# USB-interface.net
KiCad netlist of a schematic drawn in Altium Designer
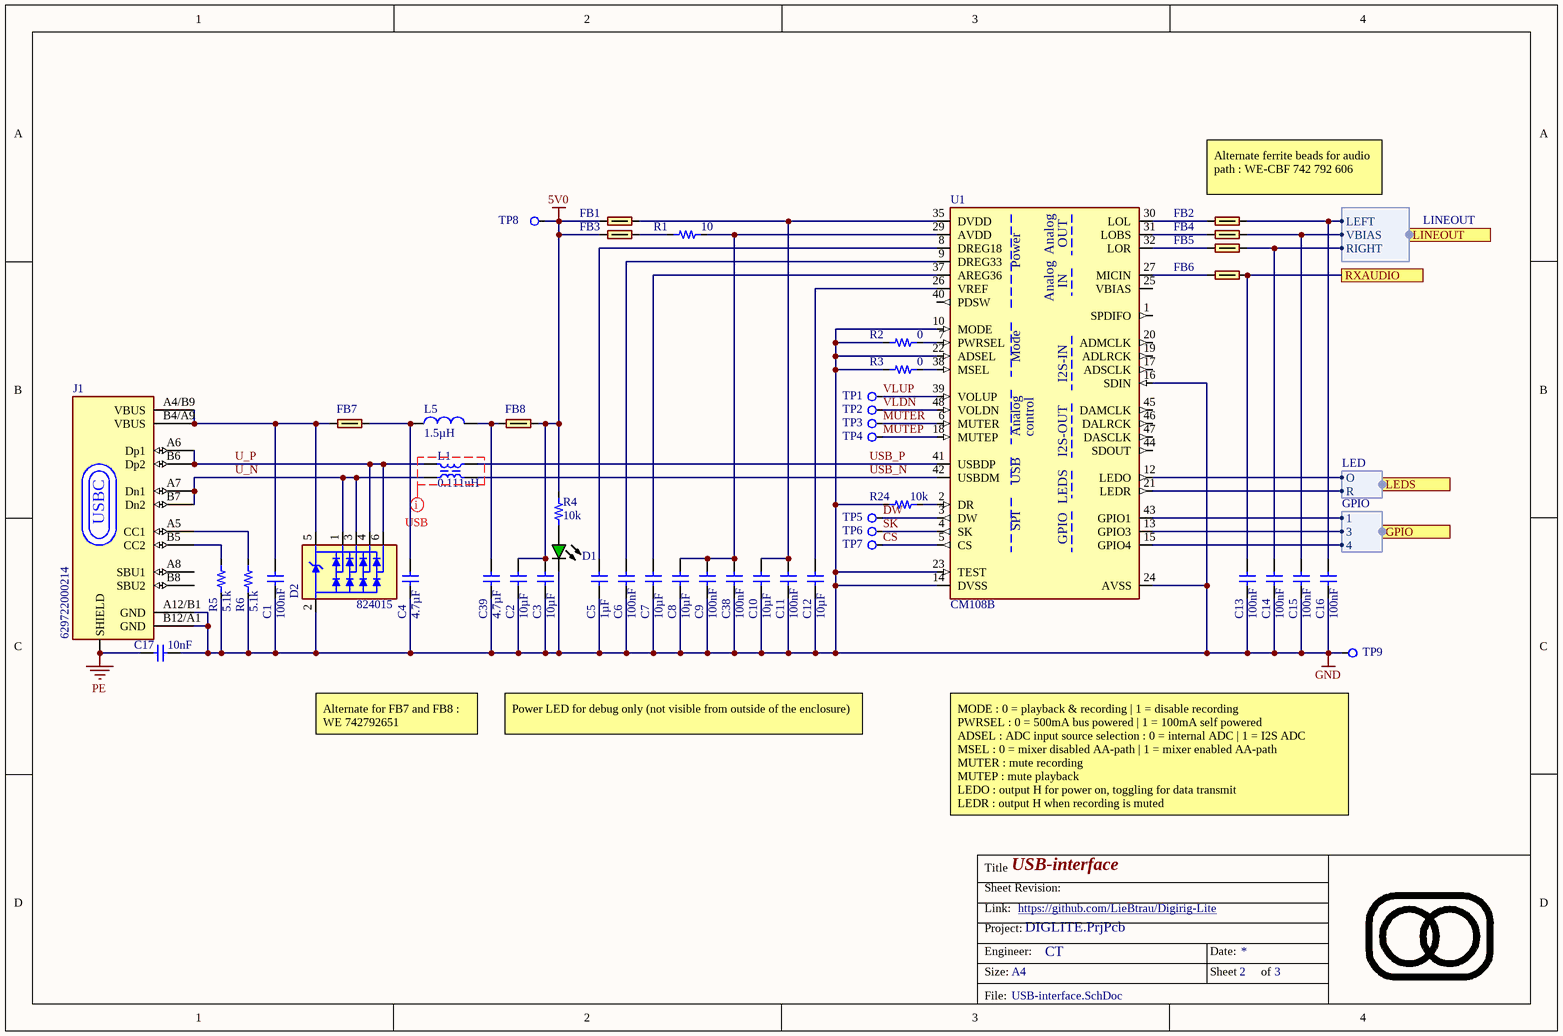
[diagram p0: USB-interface.SchDoc]

(export (version "E")
  (design (tool "Eeschema 10.0.6"))
  (components
    (comp (ref "C1")
      (value "100nF")
      (footprint "0603-C-N")
      (description "WCAP-CSGP Multilayer Ceramic Chip Capacitor, General Purpose, size 0603, X7R, 100nF, 50VDC")
      (fields (field (name "TOLERANCE") "10%") (field (name "JLCPCB PART #") "C14663"))
      (libsource (lib "7c7 Engineering") (part "CAP-NP-2"))
    )
    (comp (ref "C2")
      (value "10µF")
      (footprint "WCAP-CSGP_1210_L3.2W2.5H2.5")
      (description "WCAP-CSGP Multilayer Ceramic Chip Capacitor, General Purpose, size 1210, X7R, 10µF, 50VDC")
      (fields (field (name "TOLERANCE") "10%") (field (name "JLCPCB PART #") "C77102"))
      (libsource (lib "7c7 Engineering") (part "CAP-NP-2"))
    )
    (comp (ref "C3")
      (value "10µF")
      (footprint "WCAP-CSGP_1210_L3.2W2.5H2.5")
      (description "WCAP-CSGP Multilayer Ceramic Chip Capacitor, General Purpose, size 1210, X7R, 10µF, 50VDC")
      (fields (field (name "TOLERANCE") "10%") (field (name "JLCPCB PART #") "C77102"))
      (libsource (lib "7c7 Engineering") (part "CAP-NP-2"))
    )
    (comp (ref "C4")
      (value "4.7µF")
      (footprint "1206-C-N")
      (description "WCAP-CSGP Multilayer Ceramic Chip Capacitor, General Purpose, size 1206, X7R, 4.7µF, 10VDC")
      (fields (field (name "TOLERANCE") "10%") (field (name "JLCPCB BASIC PART") "Yes"))
      (libsource (lib "7c7 Engineering") (part "CAP-NP-2"))
    )
    (comp (ref "C5")
      (value "1µF")
      (footprint "0603-C-N")
      (description "Capacitor MLCC, General Purpose, size 0603, X7R, 1µF, +/-10%, 16V")
      (fields (field (name "TOLERANCE") "10%") (field (name "JLCPCB PART #") "C15849"))
      (libsource (lib "7c7 Engineering") (part "CAP-NP-2"))
    )
    (comp (ref "C6")
      (value "100nF")
      (footprint "0603-C-N")
      (description "WCAP-CSGP Multilayer Ceramic Chip Capacitor, General Purpose, size 0603, X7R, 100nF, 50VDC")
      (fields (field (name "TOLERANCE") "10%") (field (name "JLCPCB PART #") "C14663"))
      (libsource (lib "7c7 Engineering") (part "CAP-NP-2"))
    )
    (comp (ref "C7")
      (value "10µF")
      (footprint "WCAP-CSGP_1210_L3.2W2.5H2.5")
      (description "WCAP-CSGP Multilayer Ceramic Chip Capacitor, General Purpose, size 1210, X7R, 10µF, 50VDC")
      (fields (field (name "TOLERANCE") "10%") (field (name "JLCPCB PART #") "C77102"))
      (libsource (lib "7c7 Engineering") (part "CAP-NP-2"))
    )
    (comp (ref "C8")
      (value "10µF")
      (footprint "WCAP-CSGP_1210_L3.2W2.5H2.5")
      (description "WCAP-CSGP Multilayer Ceramic Chip Capacitor, General Purpose, size 1210, X7R, 10µF, 50VDC")
      (fields (field (name "TOLERANCE") "10%") (field (name "JLCPCB PART #") "C77102"))
      (libsource (lib "7c7 Engineering") (part "CAP-NP-2"))
    )
    (comp (ref "C9")
      (value "100nF")
      (footprint "0603-C-N")
      (description "WCAP-CSGP Multilayer Ceramic Chip Capacitor, General Purpose, size 0603, X7R, 100nF, 50VDC")
      (fields (field (name "TOLERANCE") "10%") (field (name "JLCPCB PART #") "C14663"))
      (libsource (lib "7c7 Engineering") (part "CAP-NP-2"))
    )
    (comp (ref "C10")
      (value "10µF")
      (footprint "WCAP-CSGP_1210_L3.2W2.5H2.5")
      (description "WCAP-CSGP Multilayer Ceramic Chip Capacitor, General Purpose, size 1210, X7R, 10µF, 50VDC")
      (fields (field (name "TOLERANCE") "10%") (field (name "JLCPCB PART #") "C77102"))
      (libsource (lib "7c7 Engineering") (part "CAP-NP-2"))
    )
    (comp (ref "C11")
      (value "100nF")
      (footprint "0603-C-N")
      (description "WCAP-CSGP Multilayer Ceramic Chip Capacitor, General Purpose, size 0603, X7R, 100nF, 50VDC")
      (fields (field (name "TOLERANCE") "10%") (field (name "JLCPCB PART #") "C14663"))
      (libsource (lib "7c7 Engineering") (part "CAP-NP-2"))
    )
    (comp (ref "C12")
      (value "10µF")
      (footprint "WCAP-CSGP_1210_L3.2W2.5H2.5")
      (description "WCAP-CSGP Multilayer Ceramic Chip Capacitor, General Purpose, size 1210, X7R, 10µF, 50VDC")
      (fields (field (name "TOLERANCE") "10%") (field (name "JLCPCB PART #") "C77102"))
      (libsource (lib "7c7 Engineering") (part "CAP-NP-2"))
    )
    (comp (ref "C13")
      (value "100nF")
      (footprint "0603-C-N")
      (description "WCAP-CSGP Multilayer Ceramic Chip Capacitor, General Purpose, size 0603, X7R, 100nF, 50VDC")
      (fields (field (name "TOLERANCE") "10%") (field (name "JLCPCB PART #") "C14663"))
      (libsource (lib "7c7 Engineering") (part "CAP-NP-2"))
    )
    (comp (ref "C14")
      (value "100nF")
      (footprint "0603-C-N")
      (description "WCAP-CSGP Multilayer Ceramic Chip Capacitor, General Purpose, size 0603, X7R, 100nF, 50VDC")
      (fields (field (name "TOLERANCE") "10%") (field (name "JLCPCB PART #") "C14663"))
      (libsource (lib "7c7 Engineering") (part "CAP-NP-2"))
    )
    (comp (ref "C15")
      (value "100nF")
      (footprint "0603-C-N")
      (description "WCAP-CSGP Multilayer Ceramic Chip Capacitor, General Purpose, size 0603, X7R, 100nF, 50VDC")
      (fields (field (name "TOLERANCE") "10%") (field (name "JLCPCB PART #") "C14663"))
      (libsource (lib "7c7 Engineering") (part "CAP-NP-2"))
    )
    (comp (ref "C16")
      (value "100nF")
      (footprint "0603-C-N")
      (description "WCAP-CSGP Multilayer Ceramic Chip Capacitor, General Purpose, size 0603, X7R, 100nF, 50VDC")
      (fields (field (name "TOLERANCE") "10%") (field (name "JLCPCB PART #") "C14663"))
      (libsource (lib "7c7 Engineering") (part "CAP-NP-2"))
    )
    (comp (ref "C17")
      (value "10nF")
      (footprint "0603-C-N")
      (description "Multilayer Ceramic Capacitor, Grm Series, 0.01 F, 5%, C0g / Np0, 50 V, 0603 [1608 Metric]")
      (fields (field (name "VOLTAGE") "50V") (field (name "TOLERANCE") "5%"))
      (libsource (lib "7c7 Engineering") (part "CAP-NP-2"))
    )
    (comp (ref "C38")
      (value "100nF")
      (footprint "0603-C-N")
      (description "WCAP-CSGP Multilayer Ceramic Chip Capacitor, General Purpose, size 0603, X7R, 100nF, 50VDC")
      (fields (field (name "TOLERANCE") "10%") (field (name "JLCPCB PART #") "C14663"))
      (libsource (lib "7c7 Engineering") (part "CAP-NP-2"))
    )
    (comp (ref "C39")
      (value "4.7µF")
      (footprint "1206-C-N")
      (description "WCAP-CSGP Multilayer Ceramic Chip Capacitor, General Purpose, size 1206, X7R, 4.7µF, 10VDC")
      (fields (field (name "TOLERANCE") "10%") (field (name "JLCPCB BASIC PART") "Yes"))
      (libsource (lib "7c7 Engineering") (part "CAP-NP-2"))
    )
    (comp (ref "D1")
      (value "150060GS84000")
      (footprint "WL-SMCW_0603_150060xx8x000")
      (description "WL-SMCW Mono-color Chip LED Waterclear, size 0603, Green, 3.3V, 40°")
      (fields (field (name "JLCPCB PART #") "C7429914") (field (name "MANUFACTURER") "Wurth Elektronik"))
      (libsource (lib "7c7 Engineering") (part "LED-GREEN-2"))
    )
    (comp (ref "D2")
      (value "824015")
      (footprint "SOT-23-6")
      (description "WE-TVS TVS Diode - High Speed Series, SOT23-6L, 4+1Channel, 5Vdc")
      (fields (field (name "FLIR PART #") "YDITA20KV100A") (field (name "JLCPCB PART #") "C558418"))
      (libsource (lib "7c7 Engineering") (part "D-TVS-4CH"))
    )
    (comp (ref "FB1")
      (value "742792662")
      (footprint "0603-FB-N")
      (description "WE-CBF SMT EMI Suppression Ferrite Bead, size 0603, 1000O, 0.83A")
      (fields (field (name "JLCPCB PART #") "C180490") (field (name "MANUFACTURER") "Wurth Elektronik"))
      (libsource (lib "7c7 Engineering") (part "IND_BEAD"))
    )
    (comp (ref "FB2")
      (value "742792662")
      (footprint "0603-FB-N")
      (description "WE-CBF SMT EMI Suppression Ferrite Bead, size 0603, 1000O, 0.83A")
      (fields (field (name "JLCPCB PART #") "C180490") (field (name "MANUFACTURER") "Wurth Elektronik"))
      (libsource (lib "7c7 Engineering") (part "IND_BEAD"))
    )
    (comp (ref "FB3")
      (value "742792662")
      (footprint "0603-FB-N")
      (description "WE-CBF SMT EMI Suppression Ferrite Bead, size 0603, 1000O, 0.83A")
      (fields (field (name "JLCPCB PART #") "C180490") (field (name "MANUFACTURER") "Wurth Elektronik"))
      (libsource (lib "7c7 Engineering") (part "IND_BEAD"))
    )
    (comp (ref "FB4")
      (value "742792662")
      (footprint "0603-FB-N")
      (description "WE-CBF SMT EMI Suppression Ferrite Bead, size 0603, 1000O, 0.83A")
      (fields (field (name "JLCPCB PART #") "C180490") (field (name "MANUFACTURER") "Wurth Elektronik"))
      (libsource (lib "7c7 Engineering") (part "IND_BEAD"))
    )
    (comp (ref "FB5")
      (value "742792662")
      (footprint "0603-FB-N")
      (description "WE-CBF SMT EMI Suppression Ferrite Bead, size 0603, 1000O, 0.83A")
      (fields (field (name "JLCPCB PART #") "C180490") (field (name "MANUFACTURER") "Wurth Elektronik"))
      (libsource (lib "7c7 Engineering") (part "IND_BEAD"))
    )
    (comp (ref "FB6")
      (value "742792662")
      (footprint "0603-FB-N")
      (description "WE-CBF SMT EMI Suppression Ferrite Bead, size 0603, 1000O, 0.83A")
      (fields (field (name "JLCPCB PART #") "C180490") (field (name "MANUFACTURER") "Wurth Elektronik"))
      (libsource (lib "7c7 Engineering") (part "IND_BEAD"))
    )
    (comp (ref "FB7")
      (value "74279221111")
      (footprint "WE-CBF_1206_Medium Current")
      (description "Ferrite Beads Multi-Layer High Current 110Ohm 25% 100MHz 5.4A 0.015Ohm DCR 1206 T/R")
      (fields (field (name "JLCPCB PART #") "C85841") (field (name "MANUFACTURER") "Wurth Elektronik"))
      (libsource (lib "7c7 Engineering") (part "IND_BEAD"))
    )
    (comp (ref "FB8")
      (value "74279221111")
      (footprint "WE-CBF_1206_Medium Current")
      (description "Ferrite Beads Multi-Layer High Current 110Ohm 25% 100MHz 5.4A 0.015Ohm DCR 1206 T/R")
      (fields (field (name "JLCPCB PART #") "C85841") (field (name "MANUFACTURER") "Wurth Elektronik"))
      (libsource (lib "7c7 Engineering") (part "IND_BEAD"))
    )
    (comp (ref "J1")
      (value "629722000214")
      (footprint "629722000214")
      (description "WR-USB 2.0 Type C, Receptacle, Horizontal, SMT")
      (fields (field (name "MANUFACTURER") "Wurth Elektronik") (field (name "JLCPCB PART #") "C2982555"))
      (libsource (lib "7c7 Engineering") (part "629722000214"))
    )
    (comp (ref "L1")
      (value "744232090")
      (footprint "WE-CNSW_1206")
      (description "WE-CNSW SMT Common Mode Line Filter, size 1206, 90Ohm, 0.111uH, 50V")
      (fields (field (name "JLCPCB PART #") "C131487") (field (name "INDUCTANCE") "0.111uH"))
      (libsource (lib "7c7 Engineering") (part "CM-choke"))
    )
    (comp (ref "L5")
      (value "1.5µH")
      (footprint "WE-MAPI_2512")
      (description "Inductor Power Shielded Wirewound 1.5uH 20% 100KHz Powdered Iron 2.2A 99mOhm DCR 1008 T/R")
      (fields (field (name "TOLERANCE") "20%") (field (name "JLCPCB PART #") "C161084"))
      (libsource (lib "7c7 Engineering") (part "IND"))
    )
    (comp (ref "R1")
      (value "10")
      (footprint "0603-R-N")
      (description "Chip Resistor, Thick Film, General Purpose, 0603, 100mW, 50V, 10 Ohm, +/-1%")
      (fields (field (name "TOLERANCE") "1%") (field (name "JLCPCB PART #") "C22859"))
      (libsource (lib "7c7 Engineering") (part "RES"))
    )
    (comp (ref "R2")
      (value "0")
      (footprint "0603-R-N")
      (description "Chip Jumper, Thick Film, Jumper, 0603, 100mW, 1A, 0 Ohm, <50 mOhm")
      (fields (field (name "FLIR PART #") "YRES0E-1") (field (name "TOLERANCE") "50 mOhm"))
      (libsource (lib "7c7 Engineering") (part "RES"))
    )
    (comp (ref "R3")
      (value "0")
      (footprint "0603-R-N")
      (description "Chip Jumper, Thick Film, Jumper, 0603, 100mW, 1A, 0 Ohm, <50 mOhm")
      (fields (field (name "FLIR PART #") "YRES0E-1") (field (name "TOLERANCE") "50 mOhm"))
      (libsource (lib "7c7 Engineering") (part "RES"))
    )
    (comp (ref "R4")
      (value "10k")
      (footprint "0603-R-N")
      (description "Chip Resistor, Thick Film, General Purpose, 0603, 100mW, 50V, 10 kOhm, +/-1%")
      (fields (field (name "FLIR PART #") "YRES10K-1") (field (name "PAGE PART #") "ROQF1002"))
      (libsource (lib "7c7 Engineering") (part "RES"))
    )
    (comp (ref "R5")
      (value "5.1k")
      (footprint "0603-R-N")
      (description "Chip Resistor, Thick Film, General Purpose, 0603, 100mW, 50V, 5.1 kOhm, +/-1%")
      (fields (field (name "TOLERANCE") "1%") (field (name "JLCPCB PART #") "C23186"))
      (libsource (lib "7c7 Engineering") (part "RES"))
    )
    (comp (ref "R6")
      (value "5.1k")
      (footprint "0603-R-N")
      (description "Chip Resistor, Thick Film, General Purpose, 0603, 100mW, 50V, 5.1 kOhm, +/-1%")
      (fields (field (name "TOLERANCE") "1%") (field (name "JLCPCB PART #") "C23186"))
      (libsource (lib "7c7 Engineering") (part "RES"))
    )
    (comp (ref "R24")
      (value "10k")
      (footprint "0603-R-N")
      (description "Chip Resistor, Thick Film, General Purpose, 0603, 100mW, 50V, 10 kOhm, +/-1%")
      (fields (field (name "FLIR PART #") "YRES10K-1") (field (name "PAGE PART #") "ROQF1002"))
      (libsource (lib "7c7 Engineering") (part "RES"))
    )
    (comp (ref "TP1")
      (value "Testpad with multiple sizes")
      (footprint "TP_1.5mm_0.3mmHole")
      (description "Testpad land")
      (libsource (lib "7c7 Engineering") (part "Testpad"))
    )
    (comp (ref "TP2")
      (value "Testpad with multiple sizes")
      (footprint "TP_1.5mm_0.3mmHole")
      (description "Testpad land")
      (libsource (lib "7c7 Engineering") (part "Testpad"))
    )
    (comp (ref "TP3")
      (value "Testpad with multiple sizes")
      (footprint "TP_1.5mm_0.3mmHole")
      (description "Testpad land")
      (libsource (lib "7c7 Engineering") (part "Testpad"))
    )
    (comp (ref "TP4")
      (value "Testpad with multiple sizes")
      (footprint "TP_1.5mm_0.3mmHole")
      (description "Testpad land")
      (libsource (lib "7c7 Engineering") (part "Testpad"))
    )
    (comp (ref "TP5")
      (value "Testpad with multiple sizes")
      (footprint "TP_1.5mm_0.3mmHole")
      (description "Testpad land")
      (libsource (lib "7c7 Engineering") (part "Testpad"))
    )
    (comp (ref "TP6")
      (value "Testpad with multiple sizes")
      (footprint "TP_1.5mm_0.3mmHole")
      (description "Testpad land")
      (libsource (lib "7c7 Engineering") (part "Testpad"))
    )
    (comp (ref "TP7")
      (value "Testpad with multiple sizes")
      (footprint "TP_1.5mm_0.3mmHole")
      (description "Testpad land")
      (libsource (lib "7c7 Engineering") (part "Testpad"))
    )
    (comp (ref "TP8")
      (value "Testpad with multiple sizes")
      (footprint "TP_1.5mm_0.3mmHole")
      (description "Testpad land")
      (libsource (lib "7c7 Engineering") (part "Testpad"))
    )
    (comp (ref "TP9")
      (value "Testpad with multiple sizes")
      (footprint "TP_1.5mm_0.3mmHole")
      (description "Testpad land")
      (libsource (lib "7c7 Engineering") (part "Testpad"))
    )
    (comp (ref "U1")
      (value "CM108B")
      (footprint "TSQFP50P900X900X160-48N")
      (description "USB Audio Codec improved on CM108AH with crystal-less design")
      (fields (field (name "JLCPCB PART #") "C371347"))
      (libsource (lib "7c7 Engineering") (part "CM108B-Symbol-1"))
    )
  )
  (nets
    (net (code "4") (name "/1") (class "Default")
      (node (ref "U1") (pin "43") (pinfunction "GPIO1_43") (pintype "bidirectional"))
    )
    (net (code "5") (name "/3") (class "Default")
      (node (ref "U1") (pin "13") (pinfunction "GPIO3_13") (pintype "bidirectional"))
    )
    (net (code "6") (name "/4") (class "Default")
      (node (ref "U1") (pin "15") (pinfunction "GPIO4_15") (pintype "bidirectional"))
    )
    (net (code "7") (name "/CS") (class "Default")
      (node (ref "TP7") (pin "1") (pinfunction "Pad_1") (pintype "passive"))
      (node (ref "U1") (pin "5") (pinfunction "CS_5") (pintype "output"))
    )
    (net (code "8") (name "/DW") (class "Default")
      (node (ref "TP5") (pin "1") (pinfunction "Pad_1") (pintype "passive"))
      (node (ref "U1") (pin "3") (pinfunction "DW_3") (pintype "output"))
    )
    (net (code "9") (name "/LEFT") (class "Default")
      (node (ref "C16") (pin "1") (pinfunction "1_1") (pintype "passive"))
      (node (ref "FB2") (pin "2") (pinfunction "2_2") (pintype "passive"))
    )
    (net (code "10") (name "/MUTEP") (class "Default")
      (node (ref "TP4") (pin "1") (pinfunction "Pad_1") (pintype "passive"))
      (node (ref "U1") (pin "18") (pinfunction "MUTEP_18") (pintype "input"))
    )
    (net (code "11") (name "/MUTER") (class "Default")
      (node (ref "TP3") (pin "1") (pinfunction "Pad_1") (pintype "passive"))
      (node (ref "U1") (pin "6") (pinfunction "MUTER_6") (pintype "input"))
    )
    (net (code "12") (name "/O") (class "Default")
      (node (ref "U1") (pin "12") (pinfunction "LEDO_12") (pintype "output"))
    )
    (net (code "13") (name "/R") (class "Default")
      (node (ref "U1") (pin "21") (pinfunction "LEDR_21") (pintype "output"))
    )
    (net (code "14") (name "/RIGHT") (class "Default")
      (node (ref "C14") (pin "1") (pinfunction "1_1") (pintype "passive"))
      (node (ref "FB5") (pin "2") (pinfunction "2_2") (pintype "passive"))
    )
    (net (code "15") (name "/RXAUDIO") (class "Default")
      (node (ref "C13") (pin "1") (pinfunction "1_1") (pintype "passive"))
      (node (ref "FB6") (pin "2") (pinfunction "2_2") (pintype "passive"))
    )
    (net (code "16") (name "/SK") (class "Default")
      (node (ref "TP6") (pin "1") (pinfunction "Pad_1") (pintype "passive"))
      (node (ref "U1") (pin "4") (pinfunction "SK_4") (pintype "output"))
    )
    (net (code "17") (name "/USB_N") (class "Default")
      (node (ref "L1") (pin "3") (pinfunction "3_3") (pintype "passive"))
      (node (ref "U1") (pin "42") (pinfunction "USBDM_42") (pintype "bidirectional"))
    )
    (net (code "18") (name "/USB_P") (class "Default")
      (node (ref "L1") (pin "2") (pinfunction "2_2") (pintype "passive"))
      (node (ref "U1") (pin "41") (pinfunction "USBDP_41") (pintype "bidirectional"))
    )
    (net (code "19") (name "/U_N") (class "Default")
      (node (ref "D2") (pin "1") (pinfunction "1_1") (pintype "passive"))
      (node (ref "D2") (pin "3") (pinfunction "3_3") (pintype "passive"))
      (node (ref "J1") (pin "A7") (pinfunction "Dn1_A7") (pintype "bidirectional"))
      (node (ref "J1") (pin "B7") (pinfunction "Dn2_B7") (pintype "bidirectional"))
      (node (ref "L1") (pin "4") (pinfunction "4_4") (pintype "passive"))
    )
    (net (code "20") (name "/U_P") (class "Default")
      (node (ref "D2") (pin "4") (pinfunction "4_4") (pintype "passive"))
      (node (ref "D2") (pin "6") (pinfunction "6_6") (pintype "passive"))
      (node (ref "J1") (pin "A6") (pinfunction "Dp1_A6") (pintype "bidirectional"))
      (node (ref "J1") (pin "B6") (pinfunction "Dp2_B6") (pintype "bidirectional"))
      (node (ref "L1") (pin "1") (pinfunction "1_1") (pintype "passive"))
    )
    (net (code "21") (name "/VBIAS") (class "Default")
      (node (ref "C15") (pin "1") (pinfunction "1_1") (pintype "passive"))
      (node (ref "FB4") (pin "2") (pinfunction "2_2") (pintype "passive"))
    )
    (net (code "22") (name "/VLDN") (class "Default")
      (node (ref "TP2") (pin "1") (pinfunction "Pad_1") (pintype "passive"))
      (node (ref "U1") (pin "48") (pinfunction "VOLDN_48") (pintype "input"))
    )
    (net (code "23") (name "/VLUP") (class "Default")
      (node (ref "TP1") (pin "1") (pinfunction "Pad_1") (pintype "passive"))
      (node (ref "U1") (pin "39") (pinfunction "VOLUP_39") (pintype "input"))
    )
    (net (code "27") (name "5V0") (class "Default")
      (node (ref "C2") (pin "2") (pinfunction "2_2") (pintype "passive"))
      (node (ref "C3") (pin "2") (pinfunction "2_2") (pintype "passive"))
      (node (ref "FB1") (pin "1") (pinfunction "1_1") (pintype "passive"))
      (node (ref "FB3") (pin "1") (pinfunction "1_1") (pintype "passive"))
      (node (ref "FB8") (pin "2") (pinfunction "2_2") (pintype "passive"))
      (node (ref "R4") (pin "2") (pinfunction "2_2") (pintype "passive"))
      (node (ref "TP8") (pin "1") (pinfunction "Pad_1") (pintype "passive"))
    )
    (net (code "28") (name "GND") (class "Default")
      (node (ref "C1") (pin "1") (pinfunction "1_1") (pintype "passive"))
      (node (ref "C10") (pin "1") (pinfunction "1_1") (pintype "passive"))
      (node (ref "C11") (pin "1") (pinfunction "1_1") (pintype "passive"))
      (node (ref "C12") (pin "1") (pinfunction "1_1") (pintype "passive"))
      (node (ref "C13") (pin "2") (pinfunction "2_2") (pintype "passive"))
      (node (ref "C14") (pin "2") (pinfunction "2_2") (pintype "passive"))
      (node (ref "C15") (pin "2") (pinfunction "2_2") (pintype "passive"))
      (node (ref "C16") (pin "2") (pinfunction "2_2") (pintype "passive"))
      (node (ref "C17") (pin "2") (pinfunction "2_2") (pintype "passive"))
      (node (ref "C2") (pin "1") (pinfunction "1_1") (pintype "passive"))
      (node (ref "C3") (pin "1") (pinfunction "1_1") (pintype "passive"))
      (node (ref "C38") (pin "1") (pinfunction "1_1") (pintype "passive"))
      (node (ref "C39") (pin "1") (pinfunction "1_1") (pintype "passive"))
      (node (ref "C4") (pin "1") (pinfunction "1_1") (pintype "passive"))
      (node (ref "C5") (pin "1") (pinfunction "1_1") (pintype "passive"))
      (node (ref "C6") (pin "1") (pinfunction "1_1") (pintype "passive"))
      (node (ref "C7") (pin "1") (pinfunction "1_1") (pintype "passive"))
      (node (ref "C8") (pin "1") (pinfunction "1_1") (pintype "passive"))
      (node (ref "C9") (pin "1") (pinfunction "1_1") (pintype "passive"))
      (node (ref "D1") (pin "1") (pinfunction "K_1") (pintype "passive"))
      (node (ref "D2") (pin "2") (pinfunction "2_2") (pintype "passive"))
      (node (ref "J1") (pin "A12/B1") (pinfunction "GND_A12/B1") (pintype "passive"))
      (node (ref "J1") (pin "B12/A1") (pinfunction "GND_B12/A1") (pintype "passive"))
      (node (ref "R2") (pin "1") (pinfunction "1_1") (pintype "passive"))
      (node (ref "R24") (pin "2") (pinfunction "2_2") (pintype "passive"))
      (node (ref "R3") (pin "1") (pinfunction "1_1") (pintype "passive"))
      (node (ref "R5") (pin "1") (pinfunction "1_1") (pintype "passive"))
      (node (ref "R6") (pin "1") (pinfunction "1_1") (pintype "passive"))
      (node (ref "TP9") (pin "1") (pinfunction "Pad_1") (pintype "passive"))
      (node (ref "U1") (pin "10") (pinfunction "MODE_10") (pintype "input"))
      (node (ref "U1") (pin "14") (pinfunction "DVSS_14") (pintype "passive"))
      (node (ref "U1") (pin "16") (pinfunction "SDIN_16") (pintype "input"))
      (node (ref "U1") (pin "22") (pinfunction "ADSEL_22") (pintype "input"))
      (node (ref "U1") (pin "23") (pinfunction "TEST_23") (pintype "input"))
      (node (ref "U1") (pin "24") (pinfunction "AVSS_24") (pintype "passive"))
    )
    (net (code "29") (name "Net-(C1-Pad2)") (class "Default")
      (node (ref "C1") (pin "2") (pinfunction "2_2") (pintype "passive"))
      (node (ref "D2") (pin "5") (pinfunction "5_5") (pintype "passive"))
      (node (ref "FB7") (pin "1") (pinfunction "1_1") (pintype "passive"))
      (node (ref "J1") (pin "A4/B9") (pinfunction "VBUS_A4/B9") (pintype "passive"))
      (node (ref "J1") (pin "B4/A9") (pinfunction "VBUS_B4/A9") (pintype "passive"))
    )
    (net (code "30") (name "Net-(C4-Pad2)") (class "Default")
      (node (ref "C4") (pin "2") (pinfunction "2_2") (pintype "passive"))
      (node (ref "FB7") (pin "2") (pinfunction "2_2") (pintype "passive"))
      (node (ref "L5") (pin "1") (pinfunction "1_1") (pintype "passive"))
    )
    (net (code "31") (name "Net-(C39-Pad2)") (class "Default")
      (node (ref "C39") (pin "2") (pinfunction "2_2") (pintype "passive"))
      (node (ref "FB8") (pin "1") (pinfunction "1_1") (pintype "passive"))
      (node (ref "L5") (pin "2") (pinfunction "2_2") (pintype "passive"))
    )
    (net (code "32") (name "Net-(D1-A)") (class "Default")
      (node (ref "D1") (pin "2") (pinfunction "A_2") (pintype "passive"))
      (node (ref "R4") (pin "1") (pinfunction "1_1") (pintype "passive"))
    )
    (net (code "33") (name "Net-(FB3-Pad2)") (class "Default")
      (node (ref "FB3") (pin "2") (pinfunction "2_2") (pintype "passive"))
      (node (ref "R1") (pin "1") (pinfunction "1_1") (pintype "passive"))
    )
    (net (code "34") (name "Net-(J1-CC1)") (class "Default")
      (node (ref "J1") (pin "A5") (pinfunction "CC1_A5") (pintype "bidirectional"))
      (node (ref "R6") (pin "2") (pinfunction "2_2") (pintype "passive"))
    )
    (net (code "35") (name "Net-(J1-CC2)") (class "Default")
      (node (ref "J1") (pin "B5") (pinfunction "CC2_B5") (pintype "bidirectional"))
      (node (ref "R5") (pin "2") (pinfunction "2_2") (pintype "passive"))
    )
    (net (code "36") (name "Net-(U1-AREG36)") (class "Default")
      (node (ref "C7") (pin "2") (pinfunction "2_2") (pintype "passive"))
      (node (ref "U1") (pin "37") (pinfunction "AREG36_37") (pintype "power_in"))
    )
    (net (code "37") (name "Net-(U1-AVDD)") (class "Default")
      (node (ref "C38") (pin "2") (pinfunction "2_2") (pintype "passive"))
      (node (ref "C8") (pin "2") (pinfunction "2_2") (pintype "passive"))
      (node (ref "C9") (pin "2") (pinfunction "2_2") (pintype "passive"))
      (node (ref "R1") (pin "2") (pinfunction "2_2") (pintype "passive"))
      (node (ref "U1") (pin "29") (pinfunction "AVDD_29") (pintype "passive"))
    )
    (net (code "38") (name "Net-(U1-DR)") (class "Default")
      (node (ref "R24") (pin "1") (pinfunction "1_1") (pintype "passive"))
      (node (ref "U1") (pin "2") (pinfunction "DR_2") (pintype "input"))
    )
    (net (code "39") (name "Net-(U1-DREG18)") (class "Default")
      (node (ref "C5") (pin "2") (pinfunction "2_2") (pintype "passive"))
      (node (ref "U1") (pin "8") (pinfunction "DREG18_8") (pintype "power_in"))
    )
    (net (code "40") (name "Net-(U1-DREG33)") (class "Default")
      (node (ref "C6") (pin "2") (pinfunction "2_2") (pintype "passive"))
      (node (ref "U1") (pin "9") (pinfunction "DREG33_9") (pintype "power_in"))
    )
    (net (code "41") (name "Net-(U1-DVDD)") (class "Default")
      (node (ref "C10") (pin "2") (pinfunction "2_2") (pintype "passive"))
      (node (ref "C11") (pin "2") (pinfunction "2_2") (pintype "passive"))
      (node (ref "FB1") (pin "2") (pinfunction "2_2") (pintype "passive"))
      (node (ref "U1") (pin "35") (pinfunction "DVDD_35") (pintype "passive"))
    )
    (net (code "42") (name "Net-(U1-LOBS)") (class "Default")
      (node (ref "FB4") (pin "1") (pinfunction "1_1") (pintype "passive"))
      (node (ref "U1") (pin "31") (pinfunction "LOBS_31") (pintype "passive"))
    )
    (net (code "43") (name "Net-(U1-LOL)") (class "Default")
      (node (ref "FB2") (pin "1") (pinfunction "1_1") (pintype "passive"))
      (node (ref "U1") (pin "30") (pinfunction "LOL_30") (pintype "passive"))
    )
    (net (code "44") (name "Net-(U1-LOR)") (class "Default")
      (node (ref "FB5") (pin "1") (pinfunction "1_1") (pintype "passive"))
      (node (ref "U1") (pin "32") (pinfunction "LOR_32") (pintype "passive"))
    )
    (net (code "45") (name "Net-(U1-MICIN)") (class "Default")
      (node (ref "FB6") (pin "1") (pinfunction "1_1") (pintype "passive"))
      (node (ref "U1") (pin "27") (pinfunction "MICIN_27") (pintype "passive"))
    )
    (net (code "46") (name "Net-(U1-MSEL)") (class "Default")
      (node (ref "R3") (pin "2") (pinfunction "2_2") (pintype "passive"))
      (node (ref "U1") (pin "38") (pinfunction "MSEL_38") (pintype "input"))
    )
    (net (code "47") (name "Net-(U1-PWRSEL)") (class "Default")
      (node (ref "R2") (pin "2") (pinfunction "2_2") (pintype "passive"))
      (node (ref "U1") (pin "7") (pinfunction "PWRSEL_7") (pintype "input"))
    )
    (net (code "48") (name "Net-(U1-VREF)") (class "Default")
      (node (ref "C12") (pin "2") (pinfunction "2_2") (pintype "passive"))
      (node (ref "U1") (pin "26") (pinfunction "VREF_26") (pintype "power_in"))
    )
    (net (code "49") (name "PE") (class "Default")
      (node (ref "C17") (pin "1") (pinfunction "1_1") (pintype "passive"))
      (node (ref "J1") (pin "MNT") (pinfunction "SHIELD_MNT") (pintype "power_in"))
    )
    (net (code "50") (name "unconnected-(J1-SBU1-PadA8)") (class "Default")
      (node (ref "J1") (pin "A8") (pinfunction "SBU1_A8") (pintype "bidirectional"))
    )
    (net (code "51") (name "unconnected-(J1-SBU2-PadB8)") (class "Default")
      (node (ref "J1") (pin "B8") (pinfunction "SBU2_B8") (pintype "bidirectional"))
    )
    (net (code "52") (name "unconnected-(U1-ADLRCK-Pad19)") (class "Default")
      (node (ref "U1") (pin "19") (pinfunction "ADLRCK_19") (pintype "output"))
    )
    (net (code "53") (name "unconnected-(U1-ADMCLK-Pad20)") (class "Default")
      (node (ref "U1") (pin "20") (pinfunction "ADMCLK_20") (pintype "output"))
    )
    (net (code "54") (name "unconnected-(U1-ADSCLK-Pad17)") (class "Default")
      (node (ref "U1") (pin "17") (pinfunction "ADSCLK_17") (pintype "output"))
    )
    (net (code "55") (name "unconnected-(U1-DALRCK-Pad46)") (class "Default")
      (node (ref "U1") (pin "46") (pinfunction "DALRCK_46") (pintype "output"))
    )
    (net (code "56") (name "unconnected-(U1-DAMCLK-Pad45)") (class "Default")
      (node (ref "U1") (pin "45") (pinfunction "DAMCLK_45") (pintype "output"))
    )
    (net (code "57") (name "unconnected-(U1-DASCLK-Pad47)") (class "Default")
      (node (ref "U1") (pin "47") (pinfunction "DASCLK_47") (pintype "output"))
    )
    (net (code "58") (name "unconnected-(U1-PDSW-Pad40)") (class "Default")
      (node (ref "U1") (pin "40") (pinfunction "PDSW_40") (pintype "output"))
    )
    (net (code "59") (name "unconnected-(U1-SDOUT-Pad44)") (class "Default")
      (node (ref "U1") (pin "44") (pinfunction "SDOUT_44") (pintype "output"))
    )
    (net (code "60") (name "unconnected-(U1-SPDIFO-Pad1)") (class "Default")
      (node (ref "U1") (pin "1") (pinfunction "SPDIFO_1") (pintype "output"))
    )
    (net (code "61") (name "unconnected-(U1-VBIAS-Pad25)") (class "Default")
      (node (ref "U1") (pin "25") (pinfunction "VBIAS_25") (pintype "power_in"))
    )
  )
)
